# timerShield_r1.net
KiCad netlist of a schematic drawn in EAGLE
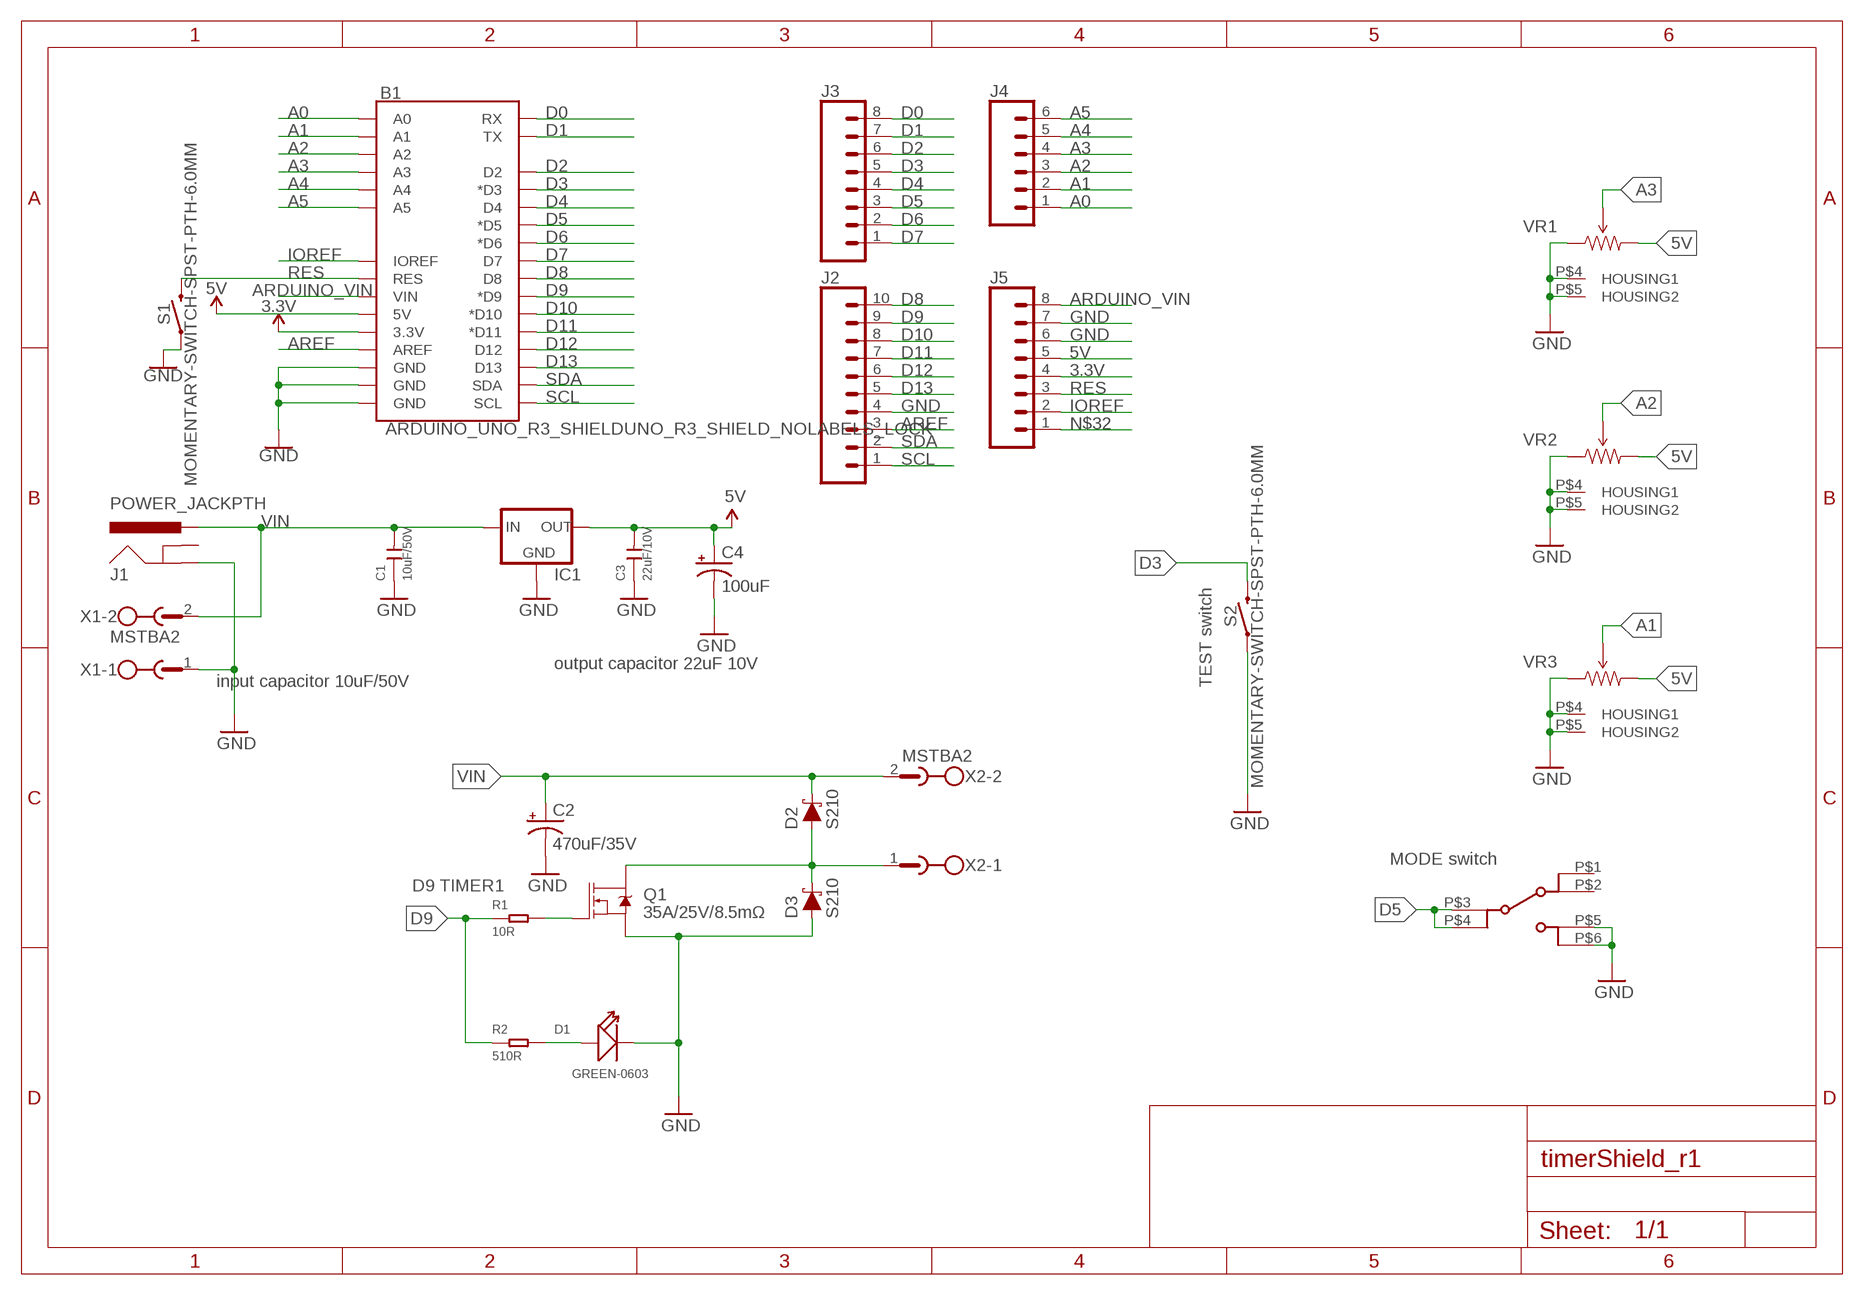
[diagram p0: schematic, sheet 1]

(export (version "E")
  (design (tool "Eeschema 10.0.6"))
  (components
    (comp (ref "B1")
      (value "ARDUINO_UNO_R3_SHIELDUNO_R3_SHIELD_NOLABELS_LOCK")
      (footprint "eagle-import:UNO_R3_SHIELD_NOLABELS_LOCK")
      (libsource (lib "eagle-import") (part "ARDUINO_UNO_R3_SHIELDUNO_R3_SHIELD_NOLABELS_LOCK"))
    )
    (comp (ref "C1")
      (value "10uF/50V")
      (footprint "eagle-import:C1206")
      (fields (field (name "MPN") "CC1206KKX5R8BB106"))
      (libsource (lib "eagle-import") (part "CERAMIC-10UF-25V-10%-X5R(1206)"))
    )
    (comp (ref "C2")
      (value "470uF/35V")
      (footprint "eagle-import:CPOL-RADIAL-5MM-10MM-KIT")
      (libsource (lib "eagle-import") (part "1000UF-RADIAL-5MM-35V-20%-KIT"))
    )
    (comp (ref "C3")
      (value "22uF/10V")
      (footprint "eagle-import:C0805")
      (fields (field (name "MPN") "CC0805MKX5R5BB226"))
      (libsource (lib "eagle-import") (part "CERAMIC-22UF-6.3V-20%-X5R(0805)"))
    )
    (comp (ref "C4")
      (value "100uF")
      (footprint "eagle-import:CPOL-RADIAL-2.5MM-6.5MM")
      (libsource (lib "eagle-import") (part "100UF-POLAR-RADIAL-2.5MM-25V-20%"))
    )
    (comp (ref "D1")
      (value "GREEN-0603")
      (footprint "eagle-import:LED-0603")
      (fields (field (name "MPN") "19-217-G7C-AN1P2-3T"))
      (libsource (lib "eagle-import") (part "SMD-LED-CLEAR-GREEN(0603)"))
    )
    (comp (ref "D2")
      (value "S210")
      (footprint "eagle-import:SMA-DIODE")
      (libsource (lib "eagle-import") (part "DIODE-SCHOTTKY-B340A"))
    )
    (comp (ref "D3")
      (value "S210")
      (footprint "eagle-import:SMA-DIODE")
      (libsource (lib "eagle-import") (part "DIODE-SCHOTTKY-B340A"))
    )
    (comp (ref "IC1")
      (value "V_REG_78XX_K78XX-500R3")
      (footprint "eagle-import:K78XX-500R3")
      (libsource (lib "eagle-import") (part "V_REG_78XX_K78XX-500R3"))
    )
    (comp (ref "J1")
      (value "POWER_JACKPTH")
      (footprint "eagle-import:POWER_JACK_PTH")
      (libsource (lib "eagle-import") (part "POWER_JACKPTH"))
    )
    (comp (ref "J2")
      (value "CONN_10\"")
      (footprint "eagle-import:1X10")
      (libsource (lib "eagle-import") (part "CONN_10{dblquote}"))
    )
    (comp (ref "J3")
      (value "CONN_08\"")
      (footprint "eagle-import:1X08")
      (libsource (lib "eagle-import") (part "CONN_08{dblquote}"))
    )
    (comp (ref "J4")
      (value "CONN_06SILK_FEMALE_PTH")
      (footprint "eagle-import:1X06")
      (libsource (lib "eagle-import") (part "CONN_06SILK_FEMALE_PTH"))
    )
    (comp (ref "J5")
      (value "CONN_08\"")
      (footprint "eagle-import:1X08")
      (libsource (lib "eagle-import") (part "CONN_08{dblquote}"))
    )
    (comp (ref "MODE")
      (value "SW_SSSS213202NARROW")
      (footprint "eagle-import:SW-SSSS213202NARROW")
      (libsource (lib "eagle-import") (part "SW_SSSS213202NARROW"))
    )
    (comp (ref "Q1")
      (value "35A/25V/8.5mΩ")
      (footprint "eagle-import:DPAK")
      (libsource (lib "eagle-import") (part "MOSFET-NCH-FDD8780"))
    )
    (comp (ref "R1")
      (value "10R")
      (footprint "eagle-import:R0603")
      (fields (field (name "MPN") "RC0603JR-0710RL"))
      (libsource (lib "eagle-import") (part "SMD-RES-10R-5%-1/10W(0603)"))
    )
    (comp (ref "R2")
      (value "510R")
      (footprint "eagle-import:R0603")
      (fields (field (name "MPN") "RC0603JR-07510RL"))
      (libsource (lib "eagle-import") (part "SMD-RES-510R-5%-1/10W(0603)"))
    )
    (comp (ref "S1")
      (value "MOMENTARY-SWITCH-SPST-PTH-6.0MM")
      (footprint "eagle-import:TACTILE_SWITCH_PTH_6.0MM")
      (libsource (lib "eagle-import") (part "MOMENTARY-SWITCH-SPST-PTH-6.0MM"))
    )
    (comp (ref "S2")
      (value "MOMENTARY-SWITCH-SPST-PTH-6.0MM")
      (footprint "eagle-import:TACTILE_SWITCH_PTH_6.0MM")
      (libsource (lib "eagle-import") (part "MOMENTARY-SWITCH-SPST-PTH-6.0MM"))
    )
    (comp (ref "VR1")
      (value "TRIMVR_HOUSING_RK09")
      (footprint "eagle-import:RK09")
      (libsource (lib "eagle-import") (part "TRIMVR_HOUSING_RK09"))
    )
    (comp (ref "VR2")
      (value "TRIMVR_HOUSING_RK09")
      (footprint "eagle-import:RK09")
      (libsource (lib "eagle-import") (part "TRIMVR_HOUSING_RK09"))
    )
    (comp (ref "VR3")
      (value "TRIMVR_HOUSING_RK09")
      (footprint "eagle-import:RK09")
      (libsource (lib "eagle-import") (part "TRIMVR_HOUSING_RK09"))
    )
    (comp (ref "X1")
      (value "MSTBA2")
      (footprint "eagle-import:MSTBA2")
      (fields (field (name "MF") "FARNELL") (field (name "MPN") "1757242"))
      (libsource (lib "eagle-import") (part "MSTBA2"))
    )
    (comp (ref "X2")
      (value "MSTBA2")
      (footprint "eagle-import:MSTBA2")
      (fields (field (name "MF") "FARNELL") (field (name "MPN") "1757242"))
      (libsource (lib "eagle-import") (part "MSTBA2"))
    )
  )
  (nets
    (net (code "1") (name "/A0") (class "Default")
      (node (ref "B1") (pin "A0") (pinfunction "A0_A0") (pintype "bidirectional"))
      (node (ref "J4") (pin "1") (pinfunction "1_1") (pintype "passive"))
    )
    (net (code "2") (name "/A4") (class "Default")
      (node (ref "B1") (pin "A4") (pinfunction "A4_A4") (pintype "bidirectional"))
      (node (ref "J4") (pin "5") (pinfunction "5_5") (pintype "passive"))
    )
    (net (code "3") (name "/A5") (class "Default")
      (node (ref "B1") (pin "A5") (pinfunction "A5_A5") (pintype "bidirectional"))
      (node (ref "J4") (pin "6") (pinfunction "6_6") (pintype "passive"))
    )
    (net (code "4") (name "/ARDUINO_VIN") (class "Default")
      (node (ref "B1") (pin "VIN") (pinfunction "VIN_VIN") (pintype "bidirectional"))
      (node (ref "J5") (pin "8") (pinfunction "8_8") (pintype "passive"))
    )
    (net (code "5") (name "/AREF") (class "Default")
      (node (ref "B1") (pin "AREF") (pinfunction "AREF_AREF") (pintype "bidirectional"))
      (node (ref "J2") (pin "3") (pinfunction "3_3") (pintype "passive"))
    )
    (net (code "6") (name "/D0") (class "Default")
      (node (ref "B1") (pin "RX") (pinfunction "RX_RX") (pintype "bidirectional"))
      (node (ref "J3") (pin "8") (pinfunction "8_8") (pintype "passive"))
    )
    (net (code "7") (name "/D1") (class "Default")
      (node (ref "B1") (pin "TX") (pinfunction "TX_TX") (pintype "bidirectional"))
      (node (ref "J3") (pin "7") (pinfunction "7_7") (pintype "passive"))
    )
    (net (code "8") (name "/D2") (class "Default")
      (node (ref "B1") (pin "D2") (pinfunction "D2_D2") (pintype "bidirectional"))
      (node (ref "J3") (pin "6") (pinfunction "6_6") (pintype "passive"))
    )
    (net (code "9") (name "/D4") (class "Default")
      (node (ref "B1") (pin "D4") (pinfunction "D4_D4") (pintype "bidirectional"))
      (node (ref "J3") (pin "4") (pinfunction "4_4") (pintype "passive"))
    )
    (net (code "10") (name "/D6") (class "Default")
      (node (ref "B1") (pin "D6") (pinfunction "*D6_D6") (pintype "bidirectional"))
      (node (ref "J3") (pin "2") (pinfunction "2_2") (pintype "passive"))
    )
    (net (code "11") (name "/D7") (class "Default")
      (node (ref "B1") (pin "D7") (pinfunction "D7_D7") (pintype "bidirectional"))
      (node (ref "J3") (pin "1") (pinfunction "1_1") (pintype "passive"))
    )
    (net (code "12") (name "/D8") (class "Default")
      (node (ref "B1") (pin "D8") (pinfunction "D8_D8") (pintype "bidirectional"))
      (node (ref "J2") (pin "10") (pinfunction "10_10") (pintype "passive"))
    )
    (net (code "13") (name "/D10") (class "Default")
      (node (ref "B1") (pin "D10") (pinfunction "*D10_D10") (pintype "bidirectional"))
      (node (ref "J2") (pin "8") (pinfunction "8_8") (pintype "passive"))
    )
    (net (code "14") (name "/D11") (class "Default")
      (node (ref "B1") (pin "D11") (pinfunction "*D11_D11") (pintype "bidirectional"))
      (node (ref "J2") (pin "7") (pinfunction "7_7") (pintype "passive"))
    )
    (net (code "15") (name "/D12") (class "Default")
      (node (ref "B1") (pin "D12") (pinfunction "D12_D12") (pintype "bidirectional"))
      (node (ref "J2") (pin "6") (pinfunction "6_6") (pintype "passive"))
    )
    (net (code "16") (name "/D13") (class "Default")
      (node (ref "B1") (pin "D13") (pinfunction "D13_D13") (pintype "bidirectional"))
      (node (ref "J2") (pin "5") (pinfunction "5_5") (pintype "passive"))
    )
    (net (code "17") (name "/IOREF") (class "Default")
      (node (ref "B1") (pin "IOREF") (pinfunction "IOREF_IOREF") (pintype "bidirectional"))
      (node (ref "J5") (pin "2") (pinfunction "2_2") (pintype "passive"))
    )
    (net (code "18") (name "/N$32") (class "Default")
      (node (ref "J5") (pin "1") (pinfunction "1_1") (pintype "passive"))
    )
    (net (code "19") (name "/RES") (class "Default")
      (node (ref "B1") (pin "RES") (pinfunction "RES_RES") (pintype "bidirectional"))
      (node (ref "J5") (pin "3") (pinfunction "3_3") (pintype "passive"))
      (node (ref "S1") (pin "3") (pinfunction "2_3") (pintype "passive"))
    )
    (net (code "20") (name "/SCL") (class "Default")
      (node (ref "B1") (pin "SCL") (pinfunction "SCL_SCL") (pintype "bidirectional"))
      (node (ref "J2") (pin "1") (pinfunction "1_1") (pintype "passive"))
    )
    (net (code "21") (name "/SDA") (class "Default")
      (node (ref "B1") (pin "SDA") (pinfunction "SDA_SDA") (pintype "bidirectional"))
      (node (ref "J2") (pin "2") (pinfunction "2_2") (pintype "passive"))
    )
    (net (code "22") (name "3.3V") (class "Default")
      (node (ref "B1") (pin "3.3V") (pinfunction "3.3V_3.3V") (pintype "bidirectional"))
      (node (ref "J5") (pin "4") (pinfunction "4_4") (pintype "passive"))
    )
    (net (code "23") (name "5V") (class "Default")
      (node (ref "B1") (pin "5V") (pinfunction "5V_5V") (pintype "bidirectional"))
      (node (ref "C3") (pin "2") (pinfunction "2_2") (pintype "passive"))
      (node (ref "C4") (pin "1") (pinfunction "+_1") (pintype "passive"))
      (node (ref "IC1") (pin "3") (pinfunction "OUT_3") (pintype "output"))
      (node (ref "J5") (pin "5") (pinfunction "5_5") (pintype "passive"))
      (node (ref "VR1") (pin "3") (pinfunction "CW_3") (pintype "passive"))
      (node (ref "VR2") (pin "3") (pinfunction "CW_3") (pintype "passive"))
      (node (ref "VR3") (pin "3") (pinfunction "CW_3") (pintype "passive"))
    )
    (net (code "24") (name "A1") (class "Default")
      (node (ref "B1") (pin "A1") (pinfunction "A1_A1") (pintype "bidirectional"))
      (node (ref "J4") (pin "2") (pinfunction "2_2") (pintype "passive"))
      (node (ref "VR3") (pin "2") (pinfunction "WIPER_2") (pintype "passive"))
    )
    (net (code "25") (name "A2") (class "Default")
      (node (ref "B1") (pin "A2") (pinfunction "A2_A2") (pintype "bidirectional"))
      (node (ref "J4") (pin "3") (pinfunction "3_3") (pintype "passive"))
      (node (ref "VR2") (pin "2") (pinfunction "WIPER_2") (pintype "passive"))
    )
    (net (code "26") (name "A3") (class "Default")
      (node (ref "B1") (pin "A3") (pinfunction "A3_A3") (pintype "bidirectional"))
      (node (ref "J4") (pin "4") (pinfunction "4_4") (pintype "passive"))
      (node (ref "VR1") (pin "2") (pinfunction "WIPER_2") (pintype "passive"))
    )
    (net (code "27") (name "D3") (class "Default")
      (node (ref "B1") (pin "D3") (pinfunction "*D3_D3") (pintype "bidirectional"))
      (node (ref "J3") (pin "5") (pinfunction "5_5") (pintype "passive"))
      (node (ref "S2") (pin "3") (pinfunction "2_3") (pintype "passive"))
    )
    (net (code "28") (name "D5") (class "Default")
      (node (ref "B1") (pin "D5") (pinfunction "*D5_D5") (pintype "bidirectional"))
      (node (ref "J3") (pin "3") (pinfunction "3_3") (pintype "passive"))
      (node (ref "MODE") (pin "P$3") (pinfunction "2-1_P$3") (pintype "bidirectional"))
      (node (ref "MODE") (pin "P$4") (pinfunction "2-2_P$4") (pintype "bidirectional"))
    )
    (net (code "29") (name "D9") (class "Default")
      (node (ref "B1") (pin "D9") (pinfunction "*D9_D9") (pintype "bidirectional"))
      (node (ref "J2") (pin "9") (pinfunction "9_9") (pintype "passive"))
      (node (ref "R1") (pin "1") (pinfunction "1_1") (pintype "passive"))
      (node (ref "R2") (pin "1") (pinfunction "1_1") (pintype "passive"))
    )
    (net (code "30") (name "GND") (class "Default")
      (node (ref "B1") (pin "GND@0") (pinfunction "GND_GND@0") (pintype "bidirectional"))
      (node (ref "B1") (pin "GND@1") (pinfunction "GND_GND@1") (pintype "bidirectional"))
      (node (ref "B1") (pin "GND@2") (pinfunction "GND_GND@2") (pintype "bidirectional"))
      (node (ref "C1") (pin "1") (pinfunction "1_1") (pintype "passive"))
      (node (ref "C2") (pin "-") (pinfunction "-_-") (pintype "passive"))
      (node (ref "C3") (pin "1") (pinfunction "1_1") (pintype "passive"))
      (node (ref "C4") (pin "2") (pinfunction "-_2") (pintype "passive"))
      (node (ref "D1") (pin "-") (pinfunction "-_-") (pintype "passive"))
      (node (ref "D3") (pin "A") (pinfunction "A_A") (pintype "passive"))
      (node (ref "IC1") (pin "2") (pinfunction "GND_2") (pintype "input"))
      (node (ref "J1") (pin "GND") (pinfunction "GND_GND") (pintype "bidirectional"))
      (node (ref "J2") (pin "4") (pinfunction "4_4") (pintype "passive"))
      (node (ref "J5") (pin "6") (pinfunction "6_6") (pintype "passive"))
      (node (ref "J5") (pin "7") (pinfunction "7_7") (pintype "passive"))
      (node (ref "MODE") (pin "P$5") (pinfunction "3-1_P$5") (pintype "bidirectional"))
      (node (ref "MODE") (pin "P$6") (pinfunction "3-2_P$6") (pintype "bidirectional"))
      (node (ref "Q1") (pin "3") (pinfunction "S_3") (pintype "bidirectional"))
      (node (ref "S1") (pin "1") (pinfunction "1_1") (pintype "passive"))
      (node (ref "S2") (pin "1") (pinfunction "1_1") (pintype "passive"))
      (node (ref "VR1") (pin "1") (pinfunction "CCW_1") (pintype "passive"))
      (node (ref "VR1") (pin "P$4") (pinfunction "HOUSING1_P$4") (pintype "passive"))
      (node (ref "VR1") (pin "P$5") (pinfunction "HOUSING2_P$5") (pintype "passive"))
      (node (ref "VR2") (pin "1") (pinfunction "CCW_1") (pintype "passive"))
      (node (ref "VR2") (pin "P$4") (pinfunction "HOUSING1_P$4") (pintype "passive"))
      (node (ref "VR2") (pin "P$5") (pinfunction "HOUSING2_P$5") (pintype "passive"))
      (node (ref "VR3") (pin "1") (pinfunction "CCW_1") (pintype "passive"))
      (node (ref "VR3") (pin "P$4") (pinfunction "HOUSING1_P$4") (pintype "passive"))
      (node (ref "VR3") (pin "P$5") (pinfunction "HOUSING2_P$5") (pintype "passive"))
      (node (ref "X1") (pin "1") (pinfunction "1_1") (pintype "passive"))
    )
    (net (code "31") (name "Net-(D1-Pad+)") (class "Default")
      (node (ref "D1") (pin "+") (pinfunction "+_+") (pintype "passive"))
      (node (ref "R2") (pin "2") (pinfunction "2_2") (pintype "passive"))
    )
    (net (code "32") (name "Net-(Q1-D)") (class "Default")
      (node (ref "D2") (pin "A") (pinfunction "A_A") (pintype "passive"))
      (node (ref "D3") (pin "C") (pinfunction "C_C") (pintype "passive"))
      (node (ref "Q1") (pin "4") (pinfunction "D_4") (pintype "bidirectional"))
      (node (ref "X2") (pin "1") (pinfunction "1_1") (pintype "passive"))
    )
    (net (code "33") (name "Net-(Q1-G)") (class "Default")
      (node (ref "Q1") (pin "1") (pinfunction "G_1") (pintype "bidirectional"))
      (node (ref "R1") (pin "2") (pinfunction "2_2") (pintype "passive"))
    )
    (net (code "34") (name "VIN") (class "Default")
      (node (ref "C1") (pin "2") (pinfunction "2_2") (pintype "passive"))
      (node (ref "C2") (pin "+") (pinfunction "+_+") (pintype "passive"))
      (node (ref "D2") (pin "C") (pinfunction "C_C") (pintype "passive"))
      (node (ref "IC1") (pin "1") (pinfunction "IN_1") (pintype "input"))
      (node (ref "J1") (pin "PWR") (pinfunction "PWR_PWR") (pintype "bidirectional"))
      (node (ref "X1") (pin "2") (pinfunction "1_2") (pintype "passive"))
      (node (ref "X2") (pin "2") (pinfunction "1_2") (pintype "passive"))
    )
    (net (code "35") (name "unconnected-(J1-PadGNDBREAK)") (class "Default")
      (node (ref "J1") (pin "GNDBREAK") (pinfunction "GNDBREAK_GNDBREAK") (pintype "bidirectional"))
    )
    (net (code "36") (name "unconnected-(MODE-1-1-PadP$1)") (class "Default")
      (node (ref "MODE") (pin "P$1") (pinfunction "1-1_P$1") (pintype "bidirectional"))
    )
    (net (code "37") (name "unconnected-(MODE-1-2-PadP$2)") (class "Default")
      (node (ref "MODE") (pin "P$2") (pinfunction "1-2_P$2") (pintype "bidirectional"))
    )
  )
)
